# MCU.net
KiCad netlist of a schematic drawn in Altium Designer
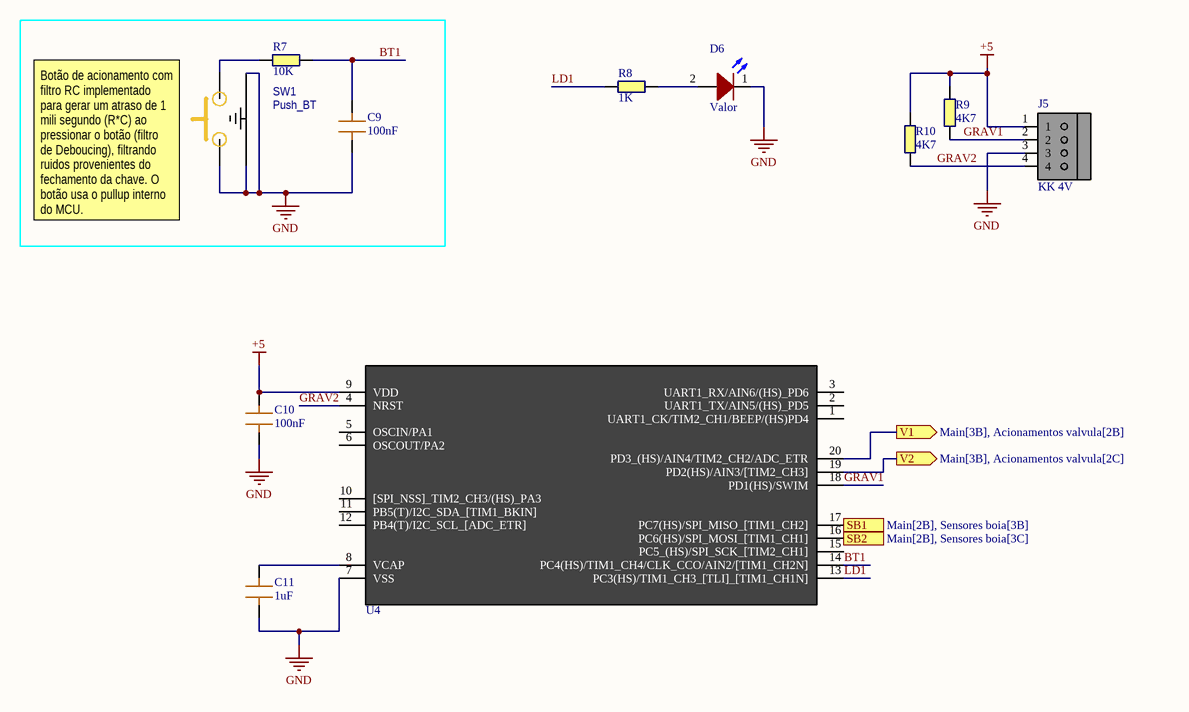
[diagram p0: MCU.SchDoc]

(export (version "E")
  (design (tool "Eeschema 10.0.6"))
  (components
    (comp (ref "C9")
      (value "100nF")
      (footprint "Capacitor 0805")
      (description "Capacitor")
      (fields (field (name "PUBLISHER") "Altium Limited"))
      (libsource (lib "Gerenciador de abastecimento") (part "CAPACITOR"))
    )
    (comp (ref "C10")
      (value "100nF")
      (footprint "Capacitor 0805")
      (description "Capacitor")
      (fields (field (name "PUBLISHER") "Altium Limited"))
      (libsource (lib "Gerenciador de abastecimento") (part "CAPACITOR"))
    )
    (comp (ref "C11")
      (value "1uF")
      (footprint "Capacitor 0805")
      (description "Capacitor")
      (fields (field (name "PUBLISHER") "Altium Limited"))
      (libsource (lib "Gerenciador de abastecimento") (part "CAPACITOR"))
    )
    (comp (ref "D6")
      (value "Valor")
      (footprint "LED 3MM")
      (description "Typical RED, GREEN, YELLOW, AMBER GaAs LED")
      (fields (field (name "PUBLISHER") "Altium Limited"))
      (libsource (lib "Gerenciador de abastecimento") (part "LED"))
    )
    (comp (ref "J5")
      (value "KK 4V")
      (footprint "CONN KK 4 VIAS")
      (libsource (lib "Gerenciador de abastecimento") (part "KK 4 vias"))
    )
    (comp (ref "R7")
      (value "10K")
      (footprint "RESISTOR 1/4W 0805")
      (description "Resistor")
      (fields (field (name "PUBLISHER") "Altium Limited"))
      (libsource (lib "") (part "RESISTOR 1/4W_2"))
    )
    (comp (ref "R8")
      (value "1K")
      (footprint "RESISTOR 1/4W 0805")
      (description "Resistor")
      (fields (field (name "PUBLISHER") "Altium Limited"))
      (libsource (lib "") (part "RESISTOR 1/4W_2"))
    )
    (comp (ref "R9")
      (value "4K7")
      (footprint "RESISTOR 1/4W 0805")
      (description "Resistor")
      (fields (field (name "PUBLISHER") "Altium Limited"))
      (libsource (lib "") (part "RESISTOR 1/4W_1"))
    )
    (comp (ref "R10")
      (value "4K7")
      (footprint "RESISTOR 1/4W 0805")
      (description "Resistor")
      (fields (field (name "PUBLISHER") "Altium Limited"))
      (libsource (lib "Gerenciador de abastecimento") (part "RESISTOR 1/4W"))
    )
    (comp (ref "SW1")
      (value "Push_BT")
      (footprint "SWITCH 9.5 180")
      (libsource (lib "Gerenciador de abastecimento") (part "Push_BT"))
    )
    (comp (ref "U4")
      (value "STM8S003F3P6")
      (footprint "SOP65P640X170-20N")
      (description "STMICROELECTRONICS - STM8S003F3P6 - MCU, 8BIT, STM8, 16MHZ, TSSOP-20")
      (fields (field (name "MOUSER PART NUMBER") "511-STM8S003F3P6"))
      (libsource (lib "Gerenciador de abastecimento") (part "STM8S003F3P6"))
    )
  )
  (nets
    (net (code "1") (name "+5") (class "Default")
      (node (ref "C10") (pin "1") (pinfunction "1_1") (pintype "passive"))
      (node (ref "J5") (pin "1") (pinfunction "1_1") (pintype "passive"))
      (node (ref "R10") (pin "2") (pinfunction "2_2") (pintype "passive"))
      (node (ref "R9") (pin "1") (pinfunction "1_1") (pintype "passive"))
      (node (ref "U4") (pin "9") (pinfunction "VDD_9") (pintype "passive"))
    )
    (net (code "2") (name "/BT1") (class "Default")
      (node (ref "C9") (pin "1") (pinfunction "1_1") (pintype "passive"))
      (node (ref "R7") (pin "1") (pinfunction "1_1") (pintype "passive"))
      (node (ref "U4") (pin "14") (pinfunction "PC4(HS)/TIM1_CH4/CLK_CCO/AIN2/[TIM1_CH2N]_14") (pintype "passive"))
    )
    (net (code "3") (name "/GRAV1") (class "Default")
      (node (ref "J5") (pin "2") (pinfunction "2_2") (pintype "passive"))
      (node (ref "R9") (pin "2") (pinfunction "2_2") (pintype "passive"))
      (node (ref "U4") (pin "18") (pinfunction "PD1(HS)/SWIM_18") (pintype "passive"))
    )
    (net (code "4") (name "/GRAV2") (class "Default")
      (node (ref "J5") (pin "4") (pinfunction "4_4") (pintype "passive"))
      (node (ref "R10") (pin "1") (pinfunction "1_1") (pintype "passive"))
      (node (ref "U4") (pin "4") (pinfunction "NRST_4") (pintype "passive"))
    )
    (net (code "5") (name "/LD1") (class "Default")
      (node (ref "R8") (pin "2") (pinfunction "2_2") (pintype "passive"))
      (node (ref "U4") (pin "13") (pinfunction "PC3(HS)/TIM1_CH3_[TLI]_[TIM1_CH1N]_13") (pintype "passive"))
    )
    (net (code "6") (name "/SB1") (class "Default")
      (node (ref "U4") (pin "17") (pinfunction "PC7(HS)/SPI_MISO_[TIM1_CH2]_17") (pintype "passive"))
    )
    (net (code "7") (name "/SB2") (class "Default")
      (node (ref "U4") (pin "16") (pinfunction "PC6(HS)/SPI_MOSI_[TIM1_CH1]_16") (pintype "passive"))
    )
    (net (code "8") (name "/V1") (class "Default")
      (node (ref "U4") (pin "20") (pinfunction "PD3_(HS)/AIN4/TIM2_CH2/ADC_ETR_20") (pintype "passive"))
    )
    (net (code "9") (name "/V2") (class "Default")
      (node (ref "U4") (pin "19") (pinfunction "PD2(HS)/AIN3/[TIM2_CH3]_19") (pintype "passive"))
    )
    (net (code "10") (name "GND") (class "Default")
      (node (ref "C10") (pin "2") (pinfunction "2_2") (pintype "passive"))
      (node (ref "C11") (pin "1") (pinfunction "1_1") (pintype "passive"))
      (node (ref "C9") (pin "2") (pinfunction "2_2") (pintype "passive"))
      (node (ref "D6") (pin "1") (pinfunction "1_1") (pintype "passive"))
      (node (ref "J5") (pin "3") (pinfunction "3_3") (pintype "passive"))
      (node (ref "SW1") (pin "1") (pinfunction "1_1") (pintype "passive"))
      (node (ref "SW1") (pin "3") (pinfunction "4_3") (pintype "passive"))
      (node (ref "SW1") (pin "4") (pinfunction "3_4") (pintype "passive"))
      (node (ref "U4") (pin "7") (pinfunction "VSS_7") (pintype "passive"))
    )
    (net (code "11") (name "Net-(D6-Pad2)") (class "Default")
      (node (ref "D6") (pin "2") (pinfunction "2_2") (pintype "passive"))
      (node (ref "R8") (pin "1") (pinfunction "1_1") (pintype "passive"))
    )
    (net (code "12") (name "Net-(R7-Pad2)") (class "Default")
      (node (ref "R7") (pin "2") (pinfunction "2_2") (pintype "passive"))
      (node (ref "SW1") (pin "2") (pinfunction "2_2") (pintype "passive"))
    )
    (net (code "13") (name "Net-(U4-VCAP)") (class "Default")
      (node (ref "C11") (pin "2") (pinfunction "2_2") (pintype "passive"))
      (node (ref "U4") (pin "8") (pinfunction "VCAP_8") (pintype "passive"))
    )
    (net (code "14") (name "unconnected-(U4-OSCIN{slash}PA1-Pad5)") (class "Default")
      (node (ref "U4") (pin "5") (pinfunction "OSCIN/PA1_5") (pintype "passive"))
    )
    (net (code "15") (name "unconnected-(U4-OSCOUT{slash}PA2-Pad6)") (class "Default")
      (node (ref "U4") (pin "6") (pinfunction "OSCOUT/PA2_6") (pintype "passive"))
    )
    (net (code "16") (name "unconnected-(U4-PB4(T){slash}I2C_SCL_[ADC_ETR]-Pad12)") (class "Default")
      (node (ref "U4") (pin "12") (pinfunction "PB4(T)/I2C_SCL_[ADC_ETR]_12") (pintype "passive"))
    )
    (net (code "17") (name "unconnected-(U4-PB5(T){slash}I2C_SDA_[TIM1_BKIN]-Pad11)") (class "Default")
      (node (ref "U4") (pin "11") (pinfunction "PB5(T)/I2C_SDA_[TIM1_BKIN]_11") (pintype "passive"))
    )
    (net (code "18") (name "unconnected-(U4-PC5_(HS){slash}SPI_SCK_[TIM2_CH1]-Pad15)") (class "Default")
      (node (ref "U4") (pin "15") (pinfunction "PC5_(HS)/SPI_SCK_[TIM2_CH1]_15") (pintype "passive"))
    )
    (net (code "19") (name "unconnected-(U4-UART1_CK{slash}TIM2_CH1{slash}BEEP{slash}(HS)PD4-Pad1)") (class "Default")
      (node (ref "U4") (pin "1") (pinfunction "UART1_CK/TIM2_CH1/BEEP/(HS)PD4_1") (pintype "passive"))
    )
    (net (code "20") (name "unconnected-(U4-UART1_RX{slash}AIN6{slash}(HS)_PD6-Pad3)") (class "Default")
      (node (ref "U4") (pin "3") (pinfunction "UART1_RX/AIN6/(HS)_PD6_3") (pintype "passive"))
    )
    (net (code "21") (name "unconnected-(U4-UART1_TX{slash}AIN5{slash}(HS)_PD5-Pad2)") (class "Default")
      (node (ref "U4") (pin "2") (pinfunction "UART1_TX/AIN5/(HS)_PD5_2") (pintype "passive"))
    )
    (net (code "22") (name "unconnected-(U4-[SPI_NSS]_TIM2_CH3{slash}(HS)_PA3-Pad10)") (class "Default")
      (node (ref "U4") (pin "10") (pinfunction "[SPI_NSS]_TIM2_CH3/(HS)_PA3_10") (pintype "passive"))
    )
  )
)
